# SCH_Pcb-buisness-card_2026-09-23.net
KiCad netlist of a schematic drawn in EasyEDA
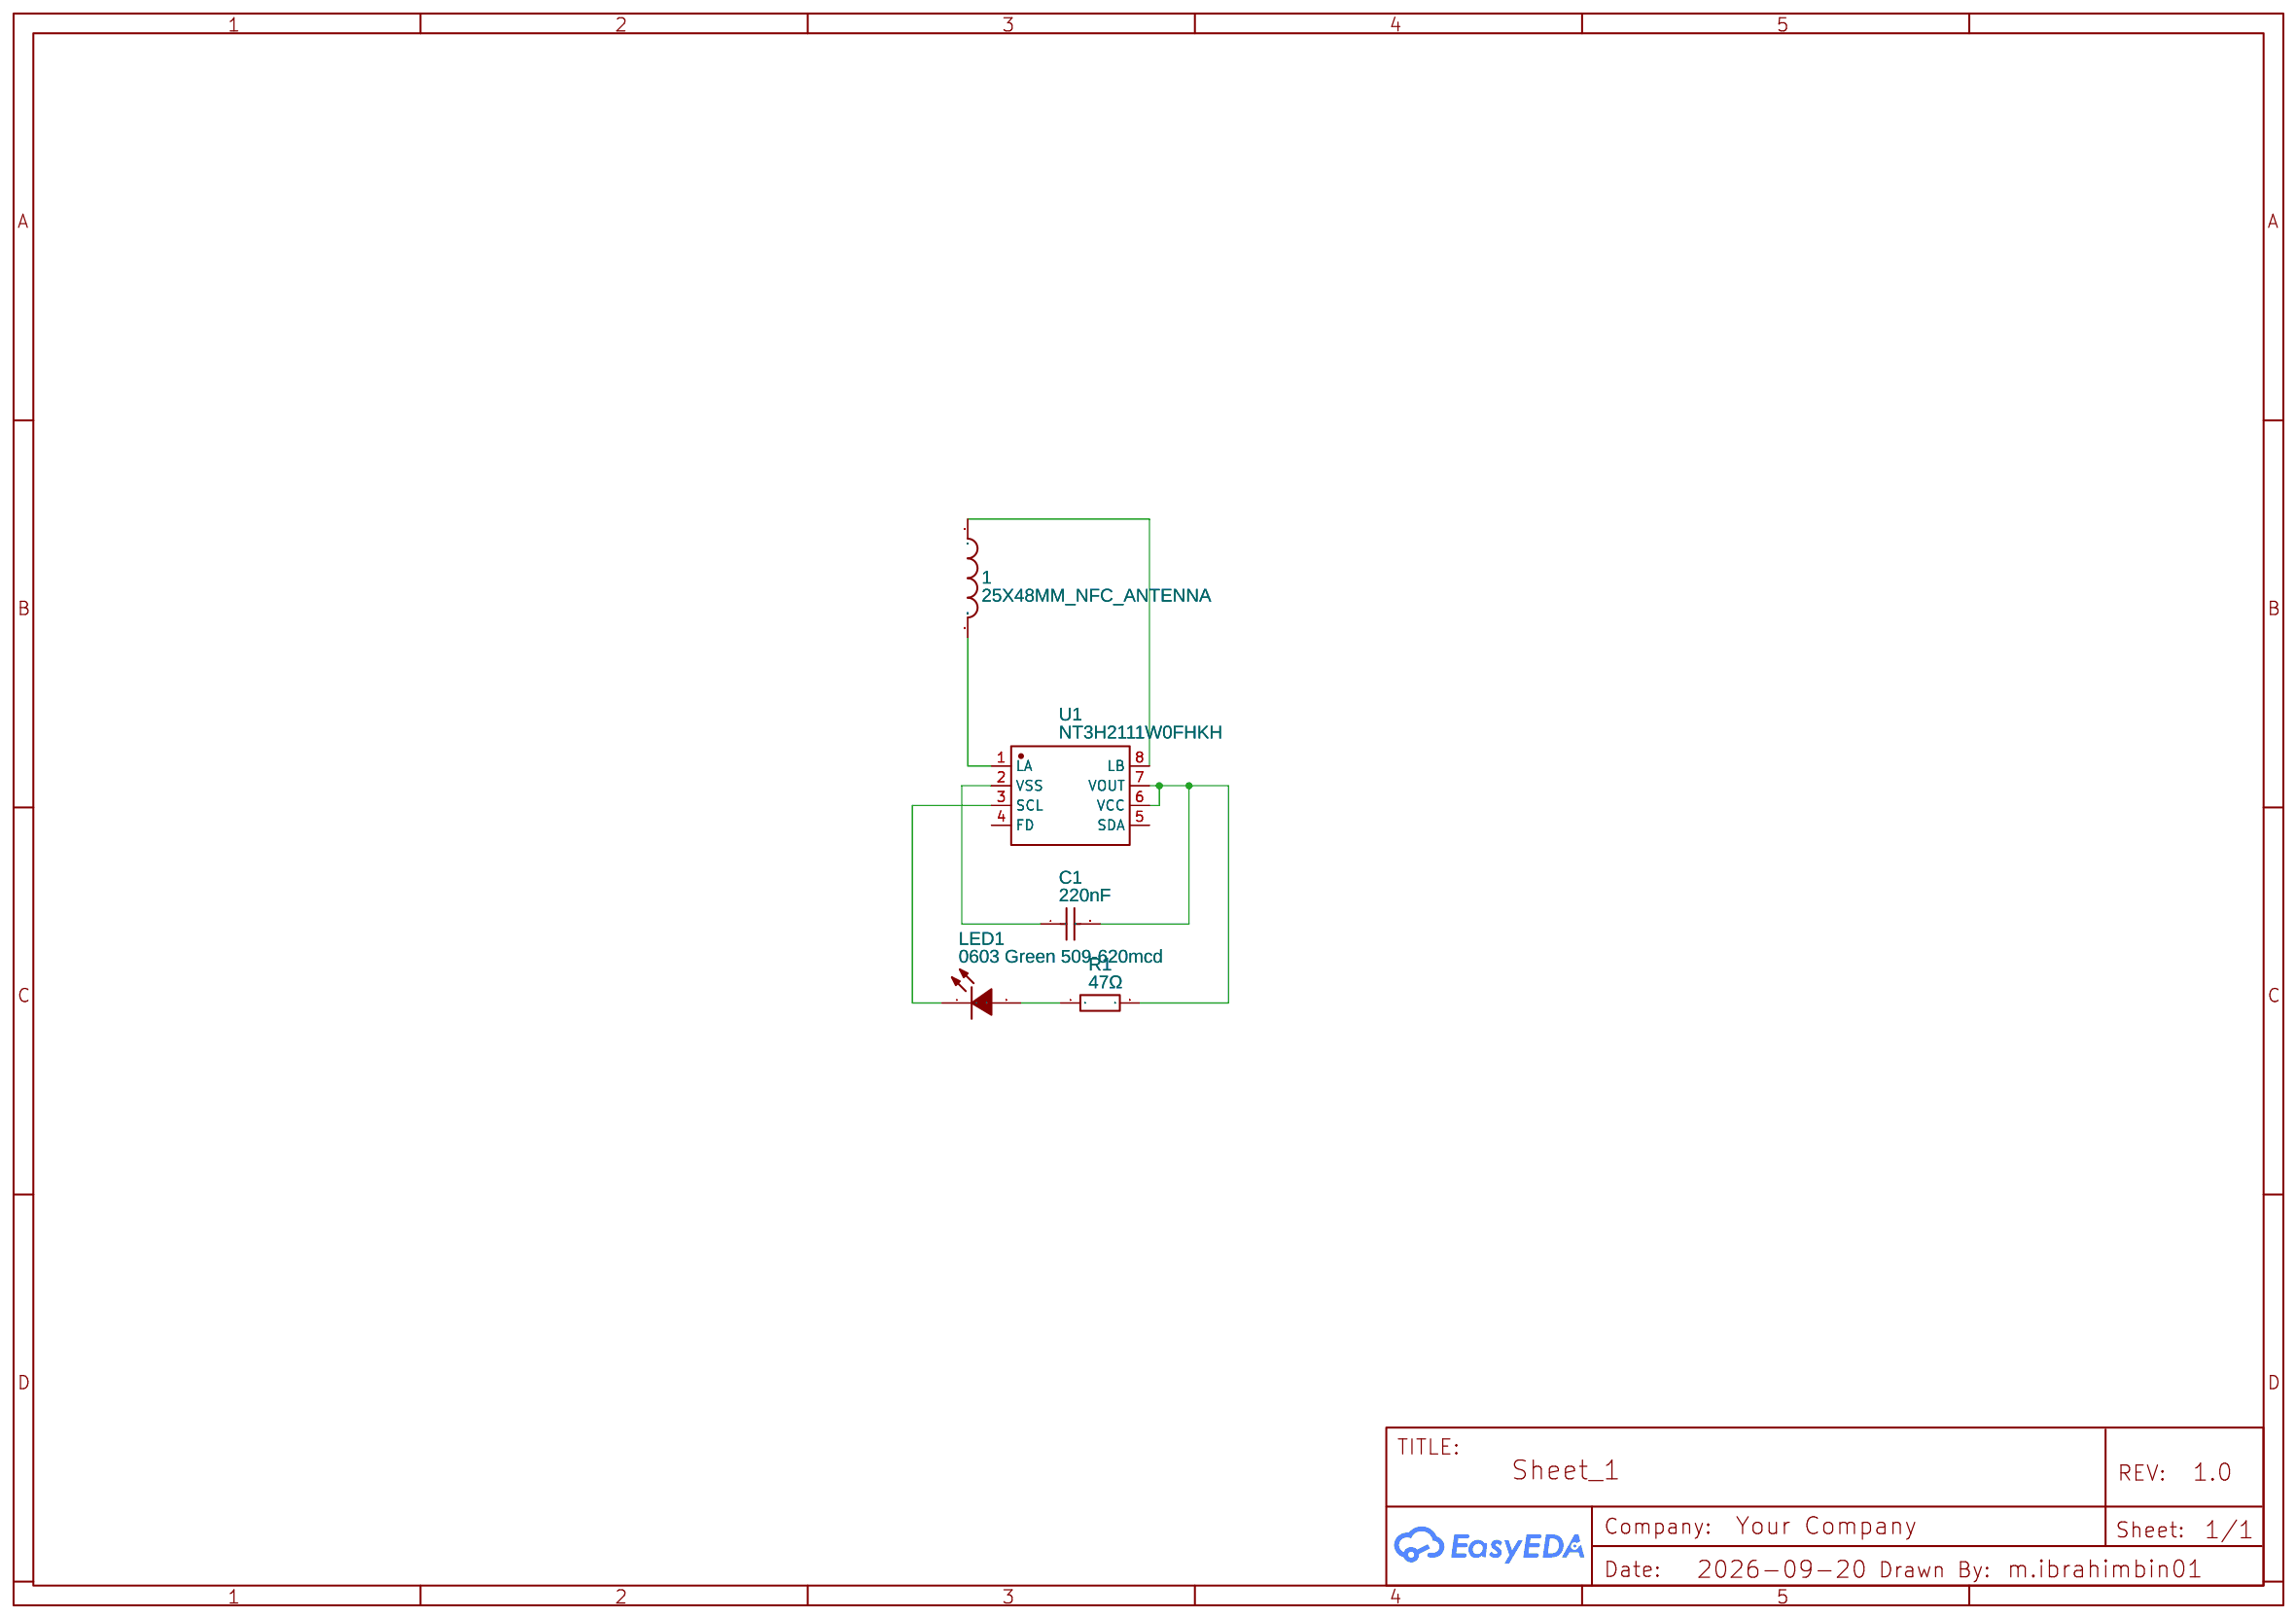
[diagram p0: schematic sheet]

(export (version "E")
  (design (tool "Eeschema 10.0.6"))
  (components
    (comp (ref "1") (value "25X48MM_NFC_ANTENNA") (libsource (lib "") (part "25X48MM_NFC_ANTENNA")))
    (comp (ref "C1")
      (value "220nF")
      (fields
        (field (name "Manufacturer Part") "CL10B224KA8NNNC")
        (field (name "Manufacturer") "SAMSUNG(三星)")
      )
      (libsource (lib "") (part "CL10B224KA8NNNC"))
    )
    (comp (ref "LED1")
      (value "0603 Green 509-620mcd")
      (fields (field (name "Manufacturer Part") "KT-0603G") (field (name "Manufacturer") "KENTO"))
      (libsource (lib "") (part "0603 Green 509-620mcd"))
    )
    (comp (ref "R1")
      (value "47Ω")
      (fields
        (field (name "Manufacturer Part") "0603WAF470JT5E")
        (field (name "Manufacturer") "UNI-ROYAL(厚声)")
      )
      (libsource (lib "") (part "0603WAF470JT5E"))
    )
    (comp (ref "U1")
      (value "NT3H2111W0FHKH")
      (fields (field (name "Manufacturer") "NXP(恩智浦)"))
      (libsource (lib "") (part "NT3H2111W0FHKH"))
    )
  )
  (nets
    (net (code "1") (name "Net-(LED1-A)") (class "Default")
      (node (ref "LED1") (pin "2") (pinfunction "A_2") (pintype "unspecified"))
      (node (ref "R1") (pin "1") (pinfunction "1_1") (pintype "input"))
    )
    (net (code "2") (name "Net-(LED1-K)") (class "Default")
      (node (ref "LED1") (pin "1") (pinfunction "K_1") (pintype "unspecified"))
      (node (ref "U1") (pin "3") (pinfunction "SCL_3") (pintype "unspecified"))
    )
    (net (code "3") (name "Net-(U1-LA)") (class "Default")
      (node (ref "1") (pin "P$2") (pinfunction "P$2_P$2") (pintype "bidirectional"))
      (node (ref "U1") (pin "1") (pinfunction "LA_1") (pintype "unspecified"))
    )
    (net (code "4") (name "Net-(U1-LB)") (class "Default")
      (node (ref "1") (pin "P$1") (pinfunction "P$1_P$1") (pintype "bidirectional"))
      (node (ref "U1") (pin "8") (pinfunction "LB_8") (pintype "unspecified"))
    )
    (net (code "5") (name "Net-(U1-VCC)") (class "Default")
      (node (ref "C1") (pin "2") (pinfunction "2_2") (pintype "input"))
      (node (ref "R1") (pin "2") (pinfunction "2_2") (pintype "input"))
      (node (ref "U1") (pin "6") (pinfunction "VCC_6") (pintype "unspecified"))
      (node (ref "U1") (pin "7") (pinfunction "VOUT_7") (pintype "unspecified"))
    )
    (net (code "6") (name "Net-(U1-VSS)") (class "Default")
      (node (ref "C1") (pin "1") (pinfunction "1_1") (pintype "input"))
      (node (ref "U1") (pin "2") (pinfunction "VSS_2") (pintype "unspecified"))
    )
    (net (code "7") (name "unconnected-(U1-FD-Pad4)") (class "Default")
      (node (ref "U1") (pin "4") (pinfunction "FD_4") (pintype "unspecified"))
    )
    (net (code "8") (name "unconnected-(U1-SDA-Pad5)") (class "Default")
      (node (ref "U1") (pin "5") (pinfunction "SDA_5") (pintype "unspecified"))
    )
  )
)
